# Assembly_Guide.net
KiCad netlist of a schematic drawn in Altium Designer
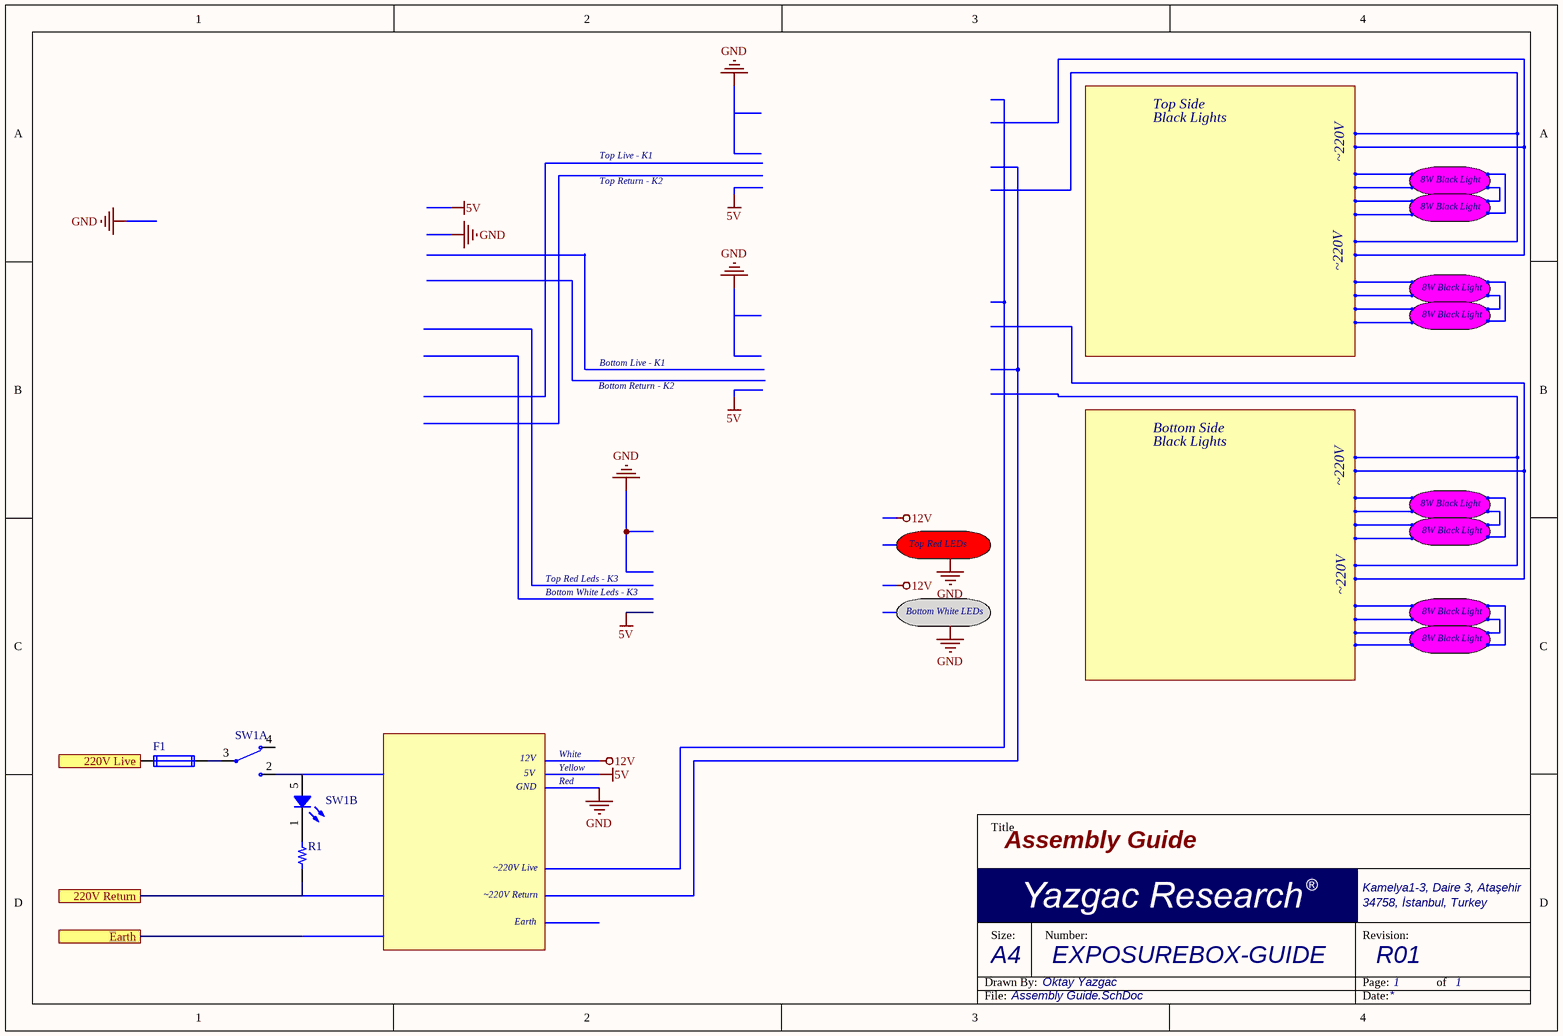
[diagram p0: Assembly Guide.SchDoc]

(export (version "E")
  (design (tool "Eeschema 10.0.6"))
  (components
    (comp (ref "F1")
      (value "~")
      (footprint "FH-100")
      (description "Fuse & Clips")
      (fields (field (name "PUBLISHER") "Altium Limited"))
      (libsource (lib "THD Miscellaneous Components") (part "Fuse"))
    )
    (comp (ref "R1")
      (value "~")
      (footprint "RES 1206/3216")
      (description "SMT Resistor")
      (libsource (lib "SMD Passive Components") (part "Resistor"))
    )
    (comp (ref "SW1")
      (value "~")
      (footprint "C&K ELUMOASAQ2C12")
      (libsource (lib "SMD Buttons") (part "PushButton C&K ELUMOASAQ2C12"))
    )
  )
  (nets
    (net (code "1") (name "/220V Live") (class "Default")
      (node (ref "F1") (pin "1") (pinfunction "1_1") (pintype "passive"))
    )
    (net (code "2") (name "/220V Return") (class "Default")
      (node (ref "R1") (pin "2") (pinfunction "2_2") (pintype "passive"))
    )
    (net (code "7") (name "Net-(SW1A-C)") (class "Default")
      (node (ref "F1") (pin "2") (pinfunction "2_2") (pintype "passive"))
      (node (ref "SW1") (pin "3") (pinfunction "C_3") (pintype "passive"))
    )
    (net (code "8") (name "Net-(SW1A-NO)") (class "Default")
      (node (ref "SW1") (pin "2") (pinfunction "NO_2") (pintype "passive"))
      (node (ref "SW1") (pin "5") (pinfunction "A_5") (pintype "passive"))
    )
    (net (code "9") (name "unconnected-(R1-Pad1)") (class "Default")
      (node (ref "R1") (pin "1") (pinfunction "1_1") (pintype "passive"))
    )
    (net (code "10") (name "unconnected-(SW1A-NC-Pad4)") (class "Default")
      (node (ref "SW1") (pin "4") (pinfunction "NC_4") (pintype "passive"))
    )
    (net (code "11") (name "unconnected-(SW1B-C-Pad1)") (class "Default")
      (node (ref "SW1") (pin "1") (pinfunction "C_1") (pintype "passive"))
    )
  )
)
